# HCSR04_RingSection_B.net
KiCad netlist of a schematic drawn in EAGLE
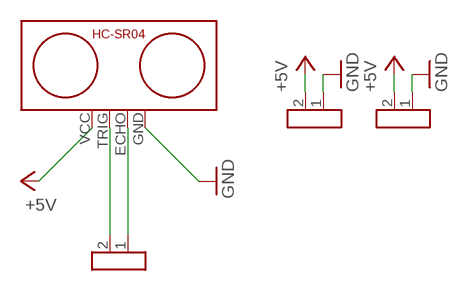
[diagram p0: schematic, sheet 1]

(export (version "E")
  (design (tool "Eeschema 10.0.6"))
  (components
    (comp (ref "U$1")
      (value "HCSR04")
      (footprint "eagle-import:HCSR04")
      (libsource (lib "eagle-import") (part "HCSR04"))
    )
    (comp (ref "U$2")
      (value "2XHEADER")
      (footprint "eagle-import:2XHEADER")
      (libsource (lib "eagle-import") (part "2XHEADER"))
    )
    (comp (ref "U$3")
      (value "2XHEADER")
      (footprint "eagle-import:2XHEADER")
      (libsource (lib "eagle-import") (part "2XHEADER"))
    )
    (comp (ref "U$4")
      (value "2XHEADER")
      (footprint "eagle-import:2XHEADER")
      (libsource (lib "eagle-import") (part "2XHEADER"))
    )
  )
  (nets
    (net (code "1") (name "+5V") (class "Default")
      (node (ref "U$1") (pin "VCC") (pinfunction "VCC_VCC") (pintype "passive"))
      (node (ref "U$2") (pin "2") (pinfunction "2_2") (pintype "passive"))
      (node (ref "U$3") (pin "2") (pinfunction "2_2") (pintype "passive"))
    )
    (net (code "2") (name "GND") (class "Default")
      (node (ref "U$1") (pin "GND") (pinfunction "GND_GND") (pintype "passive"))
      (node (ref "U$2") (pin "1") (pinfunction "1_1") (pintype "passive"))
      (node (ref "U$3") (pin "1") (pinfunction "1_1") (pintype "passive"))
    )
    (net (code "3") (name "Net-(U$1-PadECHO)") (class "Default")
      (node (ref "U$1") (pin "ECHO") (pinfunction "ECHO_ECHO") (pintype "passive"))
      (node (ref "U$4") (pin "1") (pinfunction "1_1") (pintype "passive"))
    )
    (net (code "4") (name "Net-(U$1-PadTRIG)") (class "Default")
      (node (ref "U$1") (pin "TRIG") (pinfunction "TRIG_TRIG") (pintype "passive"))
      (node (ref "U$4") (pin "2") (pinfunction "2_2") (pintype "passive"))
    )
  )
)
